# Schematic_v14.net
KiCad netlist of a schematic drawn in EAGLE
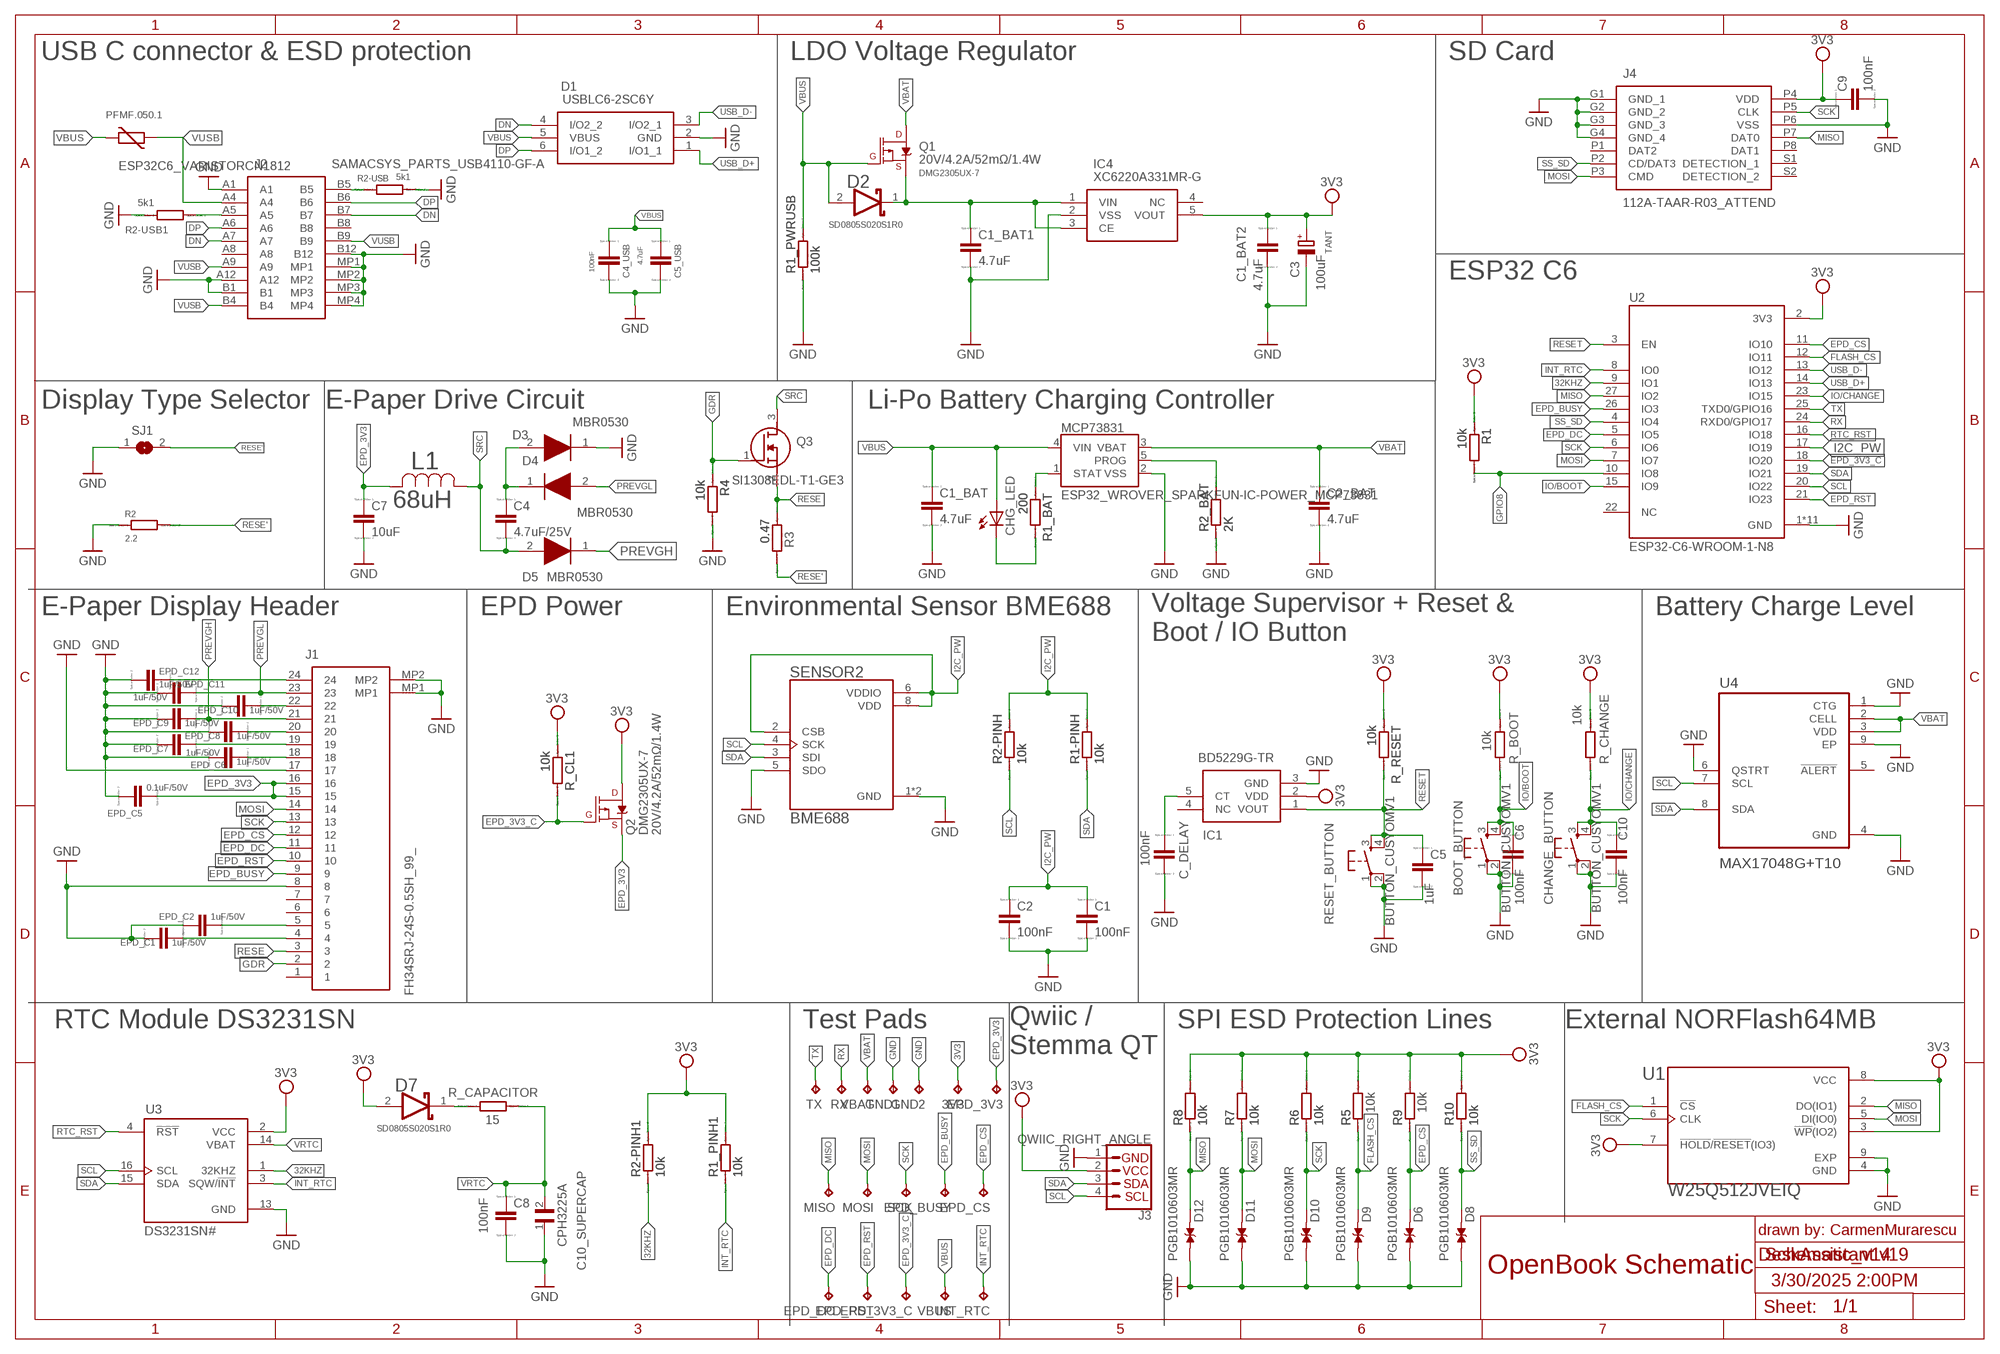
[diagram p0: schematic, sheet 1]

(export (version "E")
  (design (tool "Eeschema 10.0.6"))
  (components
    (comp (ref "3V3")
      (value "TPTP20R")
      (footprint "eagle-import:TP20R")
      (libsource (lib "eagle-import") (part "TPTP20R"))
    )
    (comp (ref "BOOT_BUTTON")
      (value "BUTTON_CUSYOMV1")
      (footprint "eagle-import:MYBUTTON")
      (libsource (lib "eagle-import") (part "BUTTON_CUSYOMV1"))
    )
    (comp (ref "C1")
      (value "100nF")
      (footprint "eagle-import:ESP32_WROVER_EAGLE-LTSPICE_C0402")
      (libsource (lib "eagle-import") (part "EAGLE-LTSPICE_CC0402"))
    )
    (comp (ref "C1_BAT")
      (value "4.7uF")
      (footprint "eagle-import:ESP32_WROVER_EAGLE-LTSPICE_C0402")
      (libsource (lib "eagle-import") (part "EAGLE-LTSPICE_CC0402"))
    )
    (comp (ref "C1_BAT1")
      (value "4.7uF")
      (footprint "eagle-import:ESP32_WROVER_EAGLE-LTSPICE_C0402")
      (libsource (lib "eagle-import") (part "ESP32_WROVER_EAGLE-LTSPICE_CC0402"))
    )
    (comp (ref "C1_BAT2")
      (value "4.7uF")
      (footprint "eagle-import:ESP32_WROVER_EAGLE-LTSPICE_C0402")
      (libsource (lib "eagle-import") (part "ESP32_WROVER_EAGLE-LTSPICE_CC0402"))
    )
    (comp (ref "C2")
      (value "100nF")
      (footprint "eagle-import:ESP32_WROVER_EAGLE-LTSPICE_C0402")
      (libsource (lib "eagle-import") (part "EAGLE-LTSPICE_CC0402"))
    )
    (comp (ref "C2_BAT")
      (value "4.7uF")
      (footprint "eagle-import:ESP32_WROVER_EAGLE-LTSPICE_C0402")
      (libsource (lib "eagle-import") (part "ESP32_WROVER_EAGLE-LTSPICE_CC0402"))
    )
    (comp (ref "C3")
      (value "100uF")
      (footprint "eagle-import:RCL_CT3528")
      (libsource (lib "eagle-import") (part "RCL_CPOL-EUCT3528"))
    )
    (comp (ref "C4")
      (value "4.7uF/25V")
      (footprint "eagle-import:ESP32_WROVER_EAGLE-LTSPICE_C0402")
      (libsource (lib "eagle-import") (part "EAGLE-LTSPICE_CC0402"))
    )
    (comp (ref "C4_USB")
      (value "100nF")
      (footprint "eagle-import:ESP32_WROVER_EAGLE-LTSPICE_C0402")
      (libsource (lib "eagle-import") (part "ESP32_WROVER_EAGLE-LTSPICE_CC0402"))
    )
    (comp (ref "C5")
      (value "1uF")
      (footprint "eagle-import:ESP32_WROVER_EAGLE-LTSPICE_C0402")
      (libsource (lib "eagle-import") (part "EAGLE-LTSPICE_CC0402"))
    )
    (comp (ref "C5_USB")
      (value "4.7uF")
      (footprint "eagle-import:ESP32_WROVER_EAGLE-LTSPICE_C0402")
      (libsource (lib "eagle-import") (part "ESP32_WROVER_EAGLE-LTSPICE_CC0402"))
    )
    (comp (ref "C6")
      (value "100nF")
      (footprint "eagle-import:ESP32_WROVER_EAGLE-LTSPICE_C0402")
      (libsource (lib "eagle-import") (part "ESP32_WROVER_EAGLE-LTSPICE_CC0402"))
    )
    (comp (ref "C7")
      (value "10uF")
      (footprint "eagle-import:ESP32_WROVER_EAGLE-LTSPICE_C0402")
      (libsource (lib "eagle-import") (part "ESP32_WROVER_EAGLE-LTSPICE_CC0402"))
    )
    (comp (ref "C8")
      (value "100nF")
      (footprint "eagle-import:ESP32_WROVER_EAGLE-LTSPICE_C0402")
      (libsource (lib "eagle-import") (part "ESP32_WROVER_EAGLE-LTSPICE_CC0402"))
    )
    (comp (ref "C9")
      (value "100nF")
      (footprint "eagle-import:ESP32_WROVER_EAGLE-LTSPICE_C0402")
      (libsource (lib "eagle-import") (part "EAGLE-LTSPICE_CC0402"))
    )
    (comp (ref "C10")
      (value "100nF")
      (footprint "eagle-import:ESP32_WROVER_EAGLE-LTSPICE_C0402")
      (libsource (lib "eagle-import") (part "ESP32_WROVER_EAGLE-LTSPICE_CC0402"))
    )
    (comp (ref "C10_SUPERCAP")
      (value "CPH3225A")
      (footprint "eagle-import:CAPCP3225X100N")
      (fields (field (name "MF") "Seiko Instruments"))
      (libsource (lib "eagle-import") (part "CPH3225A"))
    )
    (comp (ref "CHANGE_BUTTON")
      (value "BUTTON_CUSYOMV1")
      (footprint "eagle-import:MYBUTTON")
      (libsource (lib "eagle-import") (part "BUTTON_CUSYOMV1"))
    )
    (comp (ref "CHG_LED")
      (value "ADAFRUIT_LEDCHIP-LED0603")
      (footprint "eagle-import:ADAFRUIT_CHIP-LED0603")
      (libsource (lib "eagle-import") (part "ADAFRUIT_LEDCHIP-LED0603"))
    )
    (comp (ref "C_DELAY")
      (value "100nF")
      (footprint "eagle-import:ESP32_WROVER_EAGLE-LTSPICE_C0402")
      (libsource (lib "eagle-import") (part "EAGLE-LTSPICE_CC0402"))
    )
    (comp (ref "D1")
      (value "USBLC6-2SC6Y")
      (footprint "eagle-import:SOT95P280X145-6N")
      (fields (field (name "MF") "STMicroelectronics"))
      (libsource (lib "eagle-import") (part "USBLC6-2SC6Y"))
    )
    (comp (ref "D2")
      (value "ESP32_WROVER_AVX---SD0805S020S1R0_AVX_SD0805S020S1R0_0_0AVX_SD0805S020S1R0_0_0")
      (footprint "eagle-import:ESP32_WROVER_AVX---SD0805S020S1R0_AVX_SD0805S020S1R0_0")
      (fields
        (field (name "DIGIKEY_PART_NUMBER") "478-7800-1-ND")
        (field (name "MF") "AVX")
        (field (name "MOUSER_PART_NUMBER") "581-SD0805S020S1R0")
      )
      (libsource (lib "eagle-import") (part "ESP32_WROVER_AVX---SD0805S020S1R0_AVX_SD0805S020S1R0_0_0AVX_SD0805S020S1R0_0_0"))
    )
    (comp (ref "D3")
      (value "MBR0530")
      (footprint "eagle-import:SOD3716X135N")
      (fields (field (name "MF") "ON Semiconductor"))
      (libsource (lib "eagle-import") (part "MBR0530"))
    )
    (comp (ref "D4")
      (value "MBR0530")
      (footprint "eagle-import:SOD3716X135N")
      (fields (field (name "MF") "ON Semiconductor"))
      (libsource (lib "eagle-import") (part "MBR0530"))
    )
    (comp (ref "D5")
      (value "MBR0530")
      (footprint "eagle-import:SOD3716X135N")
      (fields (field (name "MF") "ON Semiconductor"))
      (libsource (lib "eagle-import") (part "MBR0530"))
    )
    (comp (ref "D6")
      (value "PGB1010603MR")
      (footprint "eagle-import:DIOC1608X36N")
      (fields (field (name "MF") "Littelfuse Inc."))
      (libsource (lib "eagle-import") (part "PGB1010603MR"))
    )
    (comp (ref "D7")
      (value "SD0805S020S1R0")
      (footprint "eagle-import:ESP32_WROVER_AVX---SD0805S020S1R0_AVX_SD0805S020S1R0_0")
      (fields
        (field (name "DIGIKEY_PART_NUMBER") "478-7800-1-ND")
        (field (name "MF") "AVX")
        (field (name "MOUSER_PART_NUMBER") "581-SD0805S020S1R0")
      )
      (libsource (lib "eagle-import") (part "ESP32_WROVER_AVX---SD0805S020S1R0_AVX_SD0805S020S1R0_0_0AVX_SD0805S020S1R0_0_0"))
    )
    (comp (ref "D8")
      (value "PGB1010603MR")
      (footprint "eagle-import:DIOC1608X36N")
      (fields (field (name "MF") "Littelfuse Inc."))
      (libsource (lib "eagle-import") (part "PGB1010603MR"))
    )
    (comp (ref "D9")
      (value "PGB1010603MR")
      (footprint "eagle-import:DIOC1608X36N")
      (fields (field (name "MF") "Littelfuse Inc."))
      (libsource (lib "eagle-import") (part "PGB1010603MR"))
    )
    (comp (ref "D10")
      (value "PGB1010603MR")
      (footprint "eagle-import:DIOC1608X36N")
      (fields (field (name "MF") "Littelfuse Inc."))
      (libsource (lib "eagle-import") (part "PGB1010603MR"))
    )
    (comp (ref "D11")
      (value "PGB1010603MR")
      (footprint "eagle-import:DIOC1608X36N")
      (fields (field (name "MF") "Littelfuse Inc."))
      (libsource (lib "eagle-import") (part "PGB1010603MR"))
    )
    (comp (ref "D12")
      (value "PGB1010603MR")
      (footprint "eagle-import:DIOC1608X36N")
      (fields (field (name "MF") "Littelfuse Inc."))
      (libsource (lib "eagle-import") (part "PGB1010603MR"))
    )
    (comp (ref "EPD_3V3")
      (value "TPTP20R")
      (footprint "eagle-import:TP20R")
      (libsource (lib "eagle-import") (part "TPTP20R"))
    )
    (comp (ref "EPD_3V3_C")
      (value "TPTP20R")
      (footprint "eagle-import:TP20R")
      (libsource (lib "eagle-import") (part "TPTP20R"))
    )
    (comp (ref "EPD_BUSY")
      (value "TPTP20R")
      (footprint "eagle-import:TP20R")
      (libsource (lib "eagle-import") (part "TPTP20R"))
    )
    (comp (ref "EPD_C1")
      (value "1uF/50V")
      (footprint "eagle-import:ESP32_WROVER_EAGLE-LTSPICE_C0402")
      (libsource (lib "eagle-import") (part "EAGLE-LTSPICE_CC0402"))
    )
    (comp (ref "EPD_C2")
      (value "1uF/50V")
      (footprint "eagle-import:ESP32_WROVER_EAGLE-LTSPICE_C0402")
      (libsource (lib "eagle-import") (part "EAGLE-LTSPICE_CC0402"))
    )
    (comp (ref "EPD_C5")
      (value "0.1uF/50V")
      (footprint "eagle-import:ESP32_WROVER_EAGLE-LTSPICE_C0402")
      (libsource (lib "eagle-import") (part "EAGLE-LTSPICE_CC0402"))
    )
    (comp (ref "EPD_C6")
      (value "1uF/50V")
      (footprint "eagle-import:ESP32_WROVER_EAGLE-LTSPICE_C0402")
      (libsource (lib "eagle-import") (part "EAGLE-LTSPICE_CC0402"))
    )
    (comp (ref "EPD_C7")
      (value "1uF/50V")
      (footprint "eagle-import:ESP32_WROVER_EAGLE-LTSPICE_C0402")
      (libsource (lib "eagle-import") (part "EAGLE-LTSPICE_CC0402"))
    )
    (comp (ref "EPD_C8")
      (value "1uF/50V")
      (footprint "eagle-import:ESP32_WROVER_EAGLE-LTSPICE_C0402")
      (libsource (lib "eagle-import") (part "EAGLE-LTSPICE_CC0402"))
    )
    (comp (ref "EPD_C9")
      (value "1uF/50V")
      (footprint "eagle-import:ESP32_WROVER_EAGLE-LTSPICE_C0402")
      (libsource (lib "eagle-import") (part "EAGLE-LTSPICE_CC0402"))
    )
    (comp (ref "EPD_C10")
      (value "1uF/50V")
      (footprint "eagle-import:ESP32_WROVER_EAGLE-LTSPICE_C0402")
      (libsource (lib "eagle-import") (part "EAGLE-LTSPICE_CC0402"))
    )
    (comp (ref "EPD_C11")
      (value "1uF/50V")
      (footprint "eagle-import:ESP32_WROVER_EAGLE-LTSPICE_C0402")
      (libsource (lib "eagle-import") (part "EAGLE-LTSPICE_CC0402"))
    )
    (comp (ref "EPD_C12")
      (value "1uF/50V")
      (footprint "eagle-import:ESP32_WROVER_EAGLE-LTSPICE_C0402")
      (libsource (lib "eagle-import") (part "EAGLE-LTSPICE_CC0402"))
    )
    (comp (ref "EPD_CS")
      (value "TPTP20R")
      (footprint "eagle-import:TP20R")
      (libsource (lib "eagle-import") (part "TPTP20R"))
    )
    (comp (ref "EPD_DC")
      (value "TPTP20R")
      (footprint "eagle-import:TP20R")
      (libsource (lib "eagle-import") (part "TPTP20R"))
    )
    (comp (ref "EPD_RST")
      (value "TPTP20R")
      (footprint "eagle-import:TP20R")
      (libsource (lib "eagle-import") (part "TPTP20R"))
    )
    (comp (ref "GND1")
      (value "TPTP20R")
      (footprint "eagle-import:TP20R")
      (libsource (lib "eagle-import") (part "TPTP20R"))
    )
    (comp (ref "GND2")
      (value "TPTP20R")
      (footprint "eagle-import:TP20R")
      (libsource (lib "eagle-import") (part "TPTP20R"))
    )
    (comp (ref "IC1")
      (value "BD5229G-TR")
      (footprint "eagle-import:SOT95P280X120-5N")
      (fields (field (name "MOUSER_PART_NUMBER") "755-BD5229G-TR"))
      (libsource (lib "eagle-import") (part "BD5229G-TR"))
    )
    (comp (ref "IC4")
      (value "XC6220A331MR-G")
      (footprint "eagle-import:SOT95P280X120-5N")
      (fields (field (name "MOUSER_PART_NUMBER") "865-XC6220A331MR-G"))
      (libsource (lib "eagle-import") (part "XC6220A331MR-G"))
    )
    (comp (ref "INT_RTC")
      (value "TPTP20R")
      (footprint "eagle-import:TP20R")
      (libsource (lib "eagle-import") (part "TPTP20R"))
    )
    (comp (ref "J1")
      (value "FH34SRJ-24S-0.5SH_99_")
      (footprint "eagle-import:FH34SRJ24S05SH99")
      (fields
        (field (name "MANUFACTURER_PART_NUMBER") "FH34SRJ-24S-0.5SH(99)")
        (field (name "MOUSER_PART_NUMBER") "798-FH34SRJ24S05SH99")
      )
      (libsource (lib "eagle-import") (part "FH34SRJ-24S-0.5SH_99_"))
    )
    (comp (ref "J2")
      (value "SAMACSYS_PARTS_USB4110-GF-A")
      (footprint "eagle-import:SAMACSYS_PARTS_USB4110GFA")
      (fields
        (field (name "MANUFACTURER_PART_NUMBER") "USB4110-GF-A")
        (field (name "MOUSER_PART_NUMBER") "640-USB4110-GF-A")
      )
      (libsource (lib "eagle-import") (part "SAMACSYS_PARTS_USB4110-GF-A"))
    )
    (comp (ref "J3")
      (value "QWIIC_RIGHT_ANGLE")
      (footprint "eagle-import:JST04_1MM_RA")
      (libsource (lib "eagle-import") (part "QWIIC_CONNECTORJS-1MM"))
    )
    (comp (ref "J4")
      (value "112A-TAAR-R03_ATTEND")
      (footprint "eagle-import:112ATAARR03ATTEND")
      (fields (field (name "MANUFACTURER_PART_NUMBER") "112A-TAAR-R03 ATTEND"))
      (libsource (lib "eagle-import") (part "112A-TAAR-R03_ATTEND"))
    )
    (comp (ref "L1")
      (value "68uH")
      (footprint "eagle-import:IND_4828-WE-TPC_WRE")
      (fields
        (field (name "MANUFACTURER_PART_NUMBER") "744043680")
        (field (name "COPYRIGHT") "Copyright (C) 2024 Ultra Librarian. All rights reserved.")
      )
      (libsource (lib "eagle-import") (part "744043680IND_4828-WE-TPC_WRE"))
    )
    (comp (ref "MCP73831")
      (value "ESP32_WROVER_SPARKFUN-IC-POWER_MCP73831")
      (footprint "eagle-import:ESP32_WROVER_SPARKFUN-IC-POWER_SOT23-5")
      (libsource (lib "eagle-import") (part "ESP32_WROVER_SPARKFUN-IC-POWER_MCP73831"))
    )
    (comp (ref "MISO")
      (value "TPTP20R")
      (footprint "eagle-import:TP20R")
      (libsource (lib "eagle-import") (part "TPTP20R"))
    )
    (comp (ref "MOSI")
      (value "TPTP20R")
      (footprint "eagle-import:TP20R")
      (libsource (lib "eagle-import") (part "TPTP20R"))
    )
    (comp (ref "PFMF.050.1")
      (value "ESP32C6_VARISTORCN1812")
      (footprint "eagle-import:ESP32C6_VARISTOR_CT_CN1812")
      (libsource (lib "eagle-import") (part "ESP32C6_VARISTORCN1812"))
    )
    (comp (ref "Q1")
      (value "20V/4.2A/52mΩ/1.4W")
      (footprint "eagle-import:ESP32_WROVER_SPARKFUN-DISCRETESEMI_SOT23-3")
      (libsource (lib "eagle-import") (part "ESP32_WROVER_SPARKFUN-DISCRETESEMI_MOSFET_PCH-DMG2305UX-7"))
    )
    (comp (ref "Q2")
      (value "20V/4.2A/52mΩ/1.4W")
      (footprint "eagle-import:ESP32_WROVER_SPARKFUN-DISCRETESEMI_SOT23-3")
      (libsource (lib "eagle-import") (part "ESP32_WROVER_SPARKFUN-DISCRETESEMI_MOSFET_PCH-DMG2305UX-7"))
    )
    (comp (ref "Q3")
      (value "SI1308EDL-T1-GE3")
      (footprint "eagle-import:SOT65P210X110-3N")
      (fields (field (name "MF") "Vishay Siliconix"))
      (libsource (lib "eagle-import") (part "SI1308EDL-T1-GE3"))
    )
    (comp (ref "R1")
      (value "10k")
      (footprint "eagle-import:ESP32_WROVER_EAGLE-LTSPICE_R0402")
      (libsource (lib "eagle-import") (part "ESP32_WROVER_EAGLE-LTSPICE_RR0402"))
    )
    (comp (ref "R1-PINH")
      (value "10k")
      (footprint "eagle-import:ESP32_WROVER_EAGLE-LTSPICE_R0402")
      (libsource (lib "eagle-import") (part "ESP32_WROVER_EAGLE-LTSPICE_RR0402"))
    )
    (comp (ref "R1_BAT")
      (value "200")
      (footprint "eagle-import:ESP32_WROVER_EAGLE-LTSPICE_R0402")
      (libsource (lib "eagle-import") (part "ESP32_WROVER_EAGLE-LTSPICE_RR0402"))
    )
    (comp (ref "R1_PINH1")
      (value "10k")
      (footprint "eagle-import:ESP32_WROVER_EAGLE-LTSPICE_R0402")
      (libsource (lib "eagle-import") (part "ESP32_WROVER_EAGLE-LTSPICE_RR0402"))
    )
    (comp (ref "R1_PWRUSB")
      (value "100k")
      (footprint "eagle-import:ESP32_WROVER_EAGLE-LTSPICE_R0402")
      (libsource (lib "eagle-import") (part "ESP32_WROVER_EAGLE-LTSPICE_RR0402"))
    )
    (comp (ref "R2")
      (value "2.2")
      (footprint "eagle-import:ESP32_WROVER_EAGLE-LTSPICE_R0402")
      (libsource (lib "eagle-import") (part "ESP32_WROVER_EAGLE-LTSPICE_RR0402"))
    )
    (comp (ref "R2-PINH")
      (value "10k")
      (footprint "eagle-import:ESP32_WROVER_EAGLE-LTSPICE_R0402")
      (libsource (lib "eagle-import") (part "ESP32_WROVER_EAGLE-LTSPICE_RR0402"))
    )
    (comp (ref "R2-PINH1")
      (value "10k")
      (footprint "eagle-import:ESP32_WROVER_EAGLE-LTSPICE_R0402")
      (libsource (lib "eagle-import") (part "ESP32_WROVER_EAGLE-LTSPICE_RR0402"))
    )
    (comp (ref "R2-USB")
      (value "5k1")
      (footprint "eagle-import:ESP32_WROVER_EAGLE-LTSPICE_R0402")
      (libsource (lib "eagle-import") (part "ESP32_WROVER_EAGLE-LTSPICE_RR0402"))
    )
    (comp (ref "R2-USB1")
      (value "5k1")
      (footprint "eagle-import:ESP32_WROVER_EAGLE-LTSPICE_R0402")
      (libsource (lib "eagle-import") (part "ESP32_WROVER_EAGLE-LTSPICE_RR0402"))
    )
    (comp (ref "R2_BAT")
      (value "2K")
      (footprint "eagle-import:ESP32_WROVER_EAGLE-LTSPICE_R0402")
      (libsource (lib "eagle-import") (part "ESP32_WROVER_EAGLE-LTSPICE_RR0402"))
    )
    (comp (ref "R3")
      (value "0.47")
      (footprint "eagle-import:ESP32_WROVER_EAGLE-LTSPICE_R0402")
      (libsource (lib "eagle-import") (part "ESP32_WROVER_EAGLE-LTSPICE_RR0402"))
    )
    (comp (ref "R4")
      (value "10k")
      (footprint "eagle-import:ESP32_WROVER_EAGLE-LTSPICE_R0402")
      (libsource (lib "eagle-import") (part "ESP32_WROVER_EAGLE-LTSPICE_RR0402"))
    )
    (comp (ref "R5")
      (value "10k")
      (footprint "eagle-import:ESP32_WROVER_EAGLE-LTSPICE_R0402")
      (libsource (lib "eagle-import") (part "ESP32_WROVER_EAGLE-LTSPICE_RR0402"))
    )
    (comp (ref "R6")
      (value "10k")
      (footprint "eagle-import:ESP32_WROVER_EAGLE-LTSPICE_R0402")
      (libsource (lib "eagle-import") (part "ESP32_WROVER_EAGLE-LTSPICE_RR0402"))
    )
    (comp (ref "R7")
      (value "10k")
      (footprint "eagle-import:ESP32_WROVER_EAGLE-LTSPICE_R0402")
      (libsource (lib "eagle-import") (part "ESP32_WROVER_EAGLE-LTSPICE_RR0402"))
    )
    (comp (ref "R8")
      (value "10k")
      (footprint "eagle-import:ESP32_WROVER_EAGLE-LTSPICE_R0402")
      (libsource (lib "eagle-import") (part "ESP32_WROVER_EAGLE-LTSPICE_RR0402"))
    )
    (comp (ref "R9")
      (value "10k")
      (footprint "eagle-import:ESP32_WROVER_EAGLE-LTSPICE_R0402")
      (libsource (lib "eagle-import") (part "ESP32_WROVER_EAGLE-LTSPICE_RR0402"))
    )
    (comp (ref "R10")
      (value "10k")
      (footprint "eagle-import:ESP32_WROVER_EAGLE-LTSPICE_R0402")
      (libsource (lib "eagle-import") (part "ESP32_WROVER_EAGLE-LTSPICE_RR0402"))
    )
    (comp (ref "RESET_BUTTON")
      (value "BUTTON_CUSYOMV1")
      (footprint "eagle-import:MYBUTTON")
      (libsource (lib "eagle-import") (part "BUTTON_CUSYOMV1"))
    )
    (comp (ref "RX")
      (value "TPTP20R")
      (footprint "eagle-import:TP20R")
      (libsource (lib "eagle-import") (part "TPTP20R"))
    )
    (comp (ref "R_BOOT")
      (value "10k")
      (footprint "eagle-import:ESP32_WROVER_EAGLE-LTSPICE_R0402")
      (libsource (lib "eagle-import") (part "ESP32_WROVER_EAGLE-LTSPICE_RR0402"))
    )
    (comp (ref "R_CAPACITOR")
      (value "15")
      (footprint "eagle-import:ESP32_WROVER_EAGLE-LTSPICE_R0402")
      (libsource (lib "eagle-import") (part "ESP32_WROVER_EAGLE-LTSPICE_RR0402"))
    )
    (comp (ref "R_CHANGE")
      (value "10k")
      (footprint "eagle-import:ESP32_WROVER_EAGLE-LTSPICE_R0402")
      (libsource (lib "eagle-import") (part "ESP32_WROVER_EAGLE-LTSPICE_RR0402"))
    )
    (comp (ref "R_CL1")
      (value "10k")
      (footprint "eagle-import:ESP32_WROVER_EAGLE-LTSPICE_R0402")
      (libsource (lib "eagle-import") (part "ESP32_WROVER_EAGLE-LTSPICE_RR0402"))
    )
    (comp (ref "R_RESET")
      (value "10k")
      (footprint "eagle-import:ESP32_WROVER_EAGLE-LTSPICE_R0402")
      (libsource (lib "eagle-import") (part "ESP32_WROVER_EAGLE-LTSPICE_RR0402"))
    )
    (comp (ref "SCK")
      (value "TPTP20R")
      (footprint "eagle-import:TP20R")
      (libsource (lib "eagle-import") (part "TPTP20R"))
    )
    (comp (ref "SENSOR2")
      (value "BME688")
      (footprint "eagle-import:ESP32_WROVER_BME680_PSON80P300X300X100-8N")
      (fields (field (name "MF") "Bosch Sensortec") (field (name "MP") "BME680"))
      (libsource (lib "eagle-import") (part "ESP32_WROVER_BME680_BME680"))
    )
    (comp (ref "SJ1") (value "SJ") (footprint "eagle-import:SJ") (libsource (lib "eagle-import") (part "SJ")))
    (comp (ref "TX")
      (value "TPTP20R")
      (footprint "eagle-import:TP20R")
      (libsource (lib "eagle-import") (part "TPTP20R"))
    )
    (comp (ref "U1")
      (value "W25Q512JVEIQ")
      (footprint "eagle-import:SON127P600X800X80-9N")
      (fields (field (name "MF") "Winbond Electronics"))
      (libsource (lib "eagle-import") (part "W25Q512JVEIQ"))
    )
    (comp (ref "U2")
      (value "ESP32-C6-WROOM-1-N8")
      (footprint "eagle-import:XCVR_ESP32-C6-WROOM-1-N8")
      (fields (field (name "MF") "Espressif Systems"))
      (libsource (lib "eagle-import") (part "ESP32-C6-WROOM-1-N8"))
    )
    (comp (ref "U3")
      (value "DS3231SN#")
      (footprint "eagle-import:SOIC127P1032X265-16N")
      (fields (field (name "MF") "Analog Devices"))
      (libsource (lib "eagle-import") (part "DS3231SN#"))
    )
    (comp (ref "U4")
      (value "MAX17048G+T10")
      (footprint "eagle-import:SON50P200X200X80-9N")
      (fields (field (name "MF") "Analog Devices"))
      (libsource (lib "eagle-import") (part "MAX17048G+T10"))
    )
    (comp (ref "VBAT")
      (value "TPTP20R")
      (footprint "eagle-import:TP20R")
      (libsource (lib "eagle-import") (part "TPTP20R"))
    )
    (comp (ref "VBUS")
      (value "TPTP20R")
      (footprint "eagle-import:TP20R")
      (libsource (lib "eagle-import") (part "TPTP20R"))
    )
  )
  (nets
    (net (code "1") (name "3V3") (class "Default")
      (node (ref "3V3") (pin "TP") (pinfunction "TP_TP") (pintype "input"))
      (node (ref "C1_BAT2") (pin "1") (pinfunction "1_1") (pintype "passive"))
      (node (ref "C3") (pin "+") (pinfunction "+_+") (pintype "passive"))
      (node (ref "C9") (pin "1") (pinfunction "1_1") (pintype "passive"))
      (node (ref "D7") (pin "2") (pinfunction "ANODE_2") (pintype "bidirectional"))
      (node (ref "IC1") (pin "2") (pinfunction "VDD_2") (pintype "bidirectional"))
      (node (ref "IC4") (pin "5") (pinfunction "VOUT_5") (pintype "bidirectional"))
      (node (ref "J3") (pin "2") (pinfunction "2_2") (pintype "power_in"))
      (node (ref "J4") (pin "P4") (pinfunction "VDD_P4") (pintype "bidirectional"))
      (node (ref "Q2") (pin "3") (pinfunction "D_3") (pintype "bidirectional"))
      (node (ref "R1") (pin "1") (pinfunction "1_1") (pintype "passive"))
      (node (ref "R10") (pin "2") (pinfunction "2_2") (pintype "passive"))
      (node (ref "R1_PINH1") (pin "2") (pinfunction "2_2") (pintype "passive"))
      (node (ref "R2-PINH1") (pin "2") (pinfunction "2_2") (pintype "passive"))
      (node (ref "R5") (pin "2") (pinfunction "2_2") (pintype "passive"))
      (node (ref "R6") (pin "2") (pinfunction "2_2") (pintype "passive"))
      (node (ref "R7") (pin "2") (pinfunction "2_2") (pintype "passive"))
      (node (ref "R8") (pin "2") (pinfunction "2_2") (pintype "passive"))
      (node (ref "R9") (pin "2") (pinfunction "2_2") (pintype "passive"))
      (node (ref "R_BOOT") (pin "2") (pinfunction "2_2") (pintype "passive"))
      (node (ref "R_CHANGE") (pin "2") (pinfunction "2_2") (pintype "passive"))
      (node (ref "R_CL1") (pin "1") (pinfunction "1_1") (pintype "passive"))
      (node (ref "R_RESET") (pin "1") (pinfunction "1_1") (pintype "passive"))
      (node (ref "U1") (pin "3") (pinfunction "~{WP}(IO2)_3") (pintype "bidirectional"))
      (node (ref "U1") (pin "7") (pinfunction "~{HOLD}/~{RESET}(IO3)_7") (pintype "bidirectional"))
      (node (ref "U1") (pin "8") (pinfunction "VCC_8") (pintype "power_in"))
      (node (ref "U2") (pin "2") (pinfunction "3V3_2") (pintype "power_in"))
      (node (ref "U3") (pin "2") (pinfunction "VCC_2") (pintype "power_in"))
    )
    (net (code "2") (name "32KHZ") (class "Default")
      (node (ref "R2-PINH1") (pin "1") (pinfunction "1_1") (pintype "passive"))
      (node (ref "U2") (pin "9") (pinfunction "IO1_9") (pintype "bidirectional"))
      (node (ref "U3") (pin "1") (pinfunction "32KHZ_1") (pintype "output"))
    )
    (net (code "3") (name "DN") (class "Default")
      (node (ref "D1") (pin "4") (pinfunction "I/O2_2_4") (pintype "bidirectional"))
      (node (ref "J2") (pin "A7") (pinfunction "A7_A7") (pintype "bidirectional"))
      (node (ref "J2") (pin "B7") (pinfunction "B7_B7") (pintype "bidirectional"))
    )
    (net (code "4") (name "DP") (class "Default")
      (node (ref "D1") (pin "6") (pinfunction "I/O1_2_6") (pintype "bidirectional"))
      (node (ref "J2") (pin "A6") (pinfunction "A6_A6") (pintype "bidirectional"))
      (node (ref "J2") (pin "B6") (pinfunction "B6_B6") (pintype "bidirectional"))
    )
    (net (code "5") (name "EPD_3V3") (class "Default")
      (node (ref "C7") (pin "1") (pinfunction "1_1") (pintype "passive"))
      (node (ref "EPD_3V3") (pin "TP") (pinfunction "TP_TP") (pintype "input"))
      (node (ref "EPD_C5") (pin "1") (pinfunction "1_1") (pintype "passive"))
      (node (ref "J1") (pin "15") (pinfunction "15_15") (pintype "bidirectional"))
      (node (ref "J1") (pin "16") (pinfunction "16_16") (pintype "bidirectional"))
      (node (ref "L1") (pin "2") (pinfunction "2_2") (pintype "passive"))
      (node (ref "Q2") (pin "2") (pinfunction "S_2") (pintype "bidirectional"))
    )
    (net (code "6") (name "EPD_3V3_C") (class "Default")
      (node (ref "EPD_3V3_C") (pin "TP") (pinfunction "TP_TP") (pintype "input"))
      (node (ref "Q2") (pin "1") (pinfunction "G_1") (pintype "bidirectional"))
      (node (ref "R_CL1") (pin "2") (pinfunction "2_2") (pintype "passive"))
      (node (ref "U2") (pin "18") (pinfunction "IO20_18") (pintype "bidirectional"))
    )
    (net (code "7") (name "EPD_BUSY") (class "Default")
      (node (ref "EPD_BUSY") (pin "TP") (pinfunction "TP_TP") (pintype "input"))
      (node (ref "J1") (pin "9") (pinfunction "9_9") (pintype "bidirectional"))
      (node (ref "U2") (pin "26") (pinfunction "IO3_26") (pintype "bidirectional"))
    )
    (net (code "8") (name "EPD_CS") (class "Default")
      (node (ref "D6") (pin "2") (pinfunction "2_2") (pintype "passive"))
      (node (ref "EPD_CS") (pin "TP") (pinfunction "TP_TP") (pintype "input"))
      (node (ref "J1") (pin "12") (pinfunction "12_12") (pintype "bidirectional"))
      (node (ref "R9") (pin "1") (pinfunction "1_1") (pintype "passive"))
      (node (ref "U2") (pin "11") (pinfunction "IO10_11") (pintype "bidirectional"))
    )
    (net (code "9") (name "EPD_DC") (class "Default")
      (node (ref "EPD_DC") (pin "TP") (pinfunction "TP_TP") (pintype "input"))
      (node (ref "J1") (pin "11") (pinfunction "11_11") (pintype "bidirectional"))
      (node (ref "U2") (pin "5") (pinfunction "IO5_5") (pintype "bidirectional"))
    )
    (net (code "10") (name "EPD_RST") (class "Default")
      (node (ref "EPD_RST") (pin "TP") (pinfunction "TP_TP") (pintype "input"))
      (node (ref "J1") (pin "10") (pinfunction "10_10") (pintype "bidirectional"))
      (node (ref "U2") (pin "21") (pinfunction "IO23_21") (pintype "bidirectional"))
    )
    (net (code "11") (name "FLASH_CS") (class "Default")
      (node (ref "D9") (pin "2") (pinfunction "2_2") (pintype "passive"))
      (node (ref "R5") (pin "1") (pinfunction "1_1") (pintype "passive"))
      (node (ref "U1") (pin "1") (pinfunction "~{CS}_1") (pintype "input"))
      (node (ref "U2") (pin "12") (pinfunction "IO11_12") (pintype "bidirectional"))
    )
    (net (code "12") (name "GDR") (class "Default")
      (node (ref "J1") (pin "2") (pinfunction "2_2") (pintype "bidirectional"))
      (node (ref "Q3") (pin "1") (pinfunction "G_1") (pintype "bidirectional"))
      (node (ref "R4") (pin "1") (pinfunction "1_1") (pintype "passive"))
    )
    (net (code "13") (name "GND") (class "Default")
      (node (ref "BOOT_BUTTON") (pin "1") (pinfunction "1_1") (pintype "passive"))
      (node (ref "BOOT_BUTTON") (pin "2") (pinfunction "2_2") (pintype "passive"))
      (node (ref "C1") (pin "2") (pinfunction "2_2") (pintype "passive"))
      (node (ref "C10") (pin "2") (pinfunction "2_2") (pintype "passive"))
      (node (ref "C10_SUPERCAP") (pin "1") (pinfunction "1_1") (pintype "passive"))
      (node (ref "C1_BAT") (pin "2") (pinfunction "2_2") (pintype "passive"))
      (node (ref "C1_BAT1") (pin "2") (pinfunction "2_2") (pintype "passive"))
      (node (ref "C1_BAT2") (pin "2") (pinfunction "2_2") (pintype "passive"))
      (node (ref "C2") (pin "2") (pinfunction "2_2") (pintype "passive"))
      (node (ref "C2_BAT") (pin "2") (pinfunction "2_2") (pintype "passive"))
      (node (ref "C3") (pin "-") (pinfunction "-_-") (pintype "passive"))
      (node (ref "C4_USB") (pin "2") (pinfunction "2_2") (pintype "passive"))
      (node (ref "C5") (pin "2") (pinfunction "2_2") (pintype "passive"))
      (node (ref "C5_USB") (pin "2") (pinfunction "2_2") (pintype "passive"))
      (node (ref "C6") (pin "2") (pinfunction "2_2") (pintype "passive"))
      (node (ref "C7") (pin "2") (pinfunction "2_2") (pintype "passive"))
      (node (ref "C8") (pin "2") (pinfunction "2_2") (pintype "passive"))
      (node (ref "C9") (pin "2") (pinfunction "2_2") (pintype "passive"))
      (node (ref "CHANGE_BUTTON") (pin "1") (pinfunction "1_1") (pintype "passive"))
      (node (ref "CHANGE_BUTTON") (pin "2") (pinfunction "2_2") (pintype "passive"))
      (node (ref "C_DELAY") (pin "2") (pinfunction "2_2") (pintype "passive"))
      (node (ref "D1") (pin "2") (pinfunction "GND_2") (pintype "bidirectional"))
      (node (ref "D10") (pin "1") (pinfunction "1_1") (pintype "passive"))
      (node (ref "D11") (pin "1") (pinfunction "1_1") (pintype "passive"))
      (node (ref "D12") (pin "1") (pinfunction "1_1") (pintype "passive"))
      (node (ref "D4") (pin "1") (pinfunction "K_1") (pintype "bidirectional"))
      (node (ref "D6") (pin "1") (pinfunction "1_1") (pintype "passive"))
      (node (ref "D8") (pin "1") (pinfunction "1_1") (pintype "passive"))
      (node (ref "D9") (pin "1") (pinfunction "1_1") (pintype "passive"))
      (node (ref "EPD_C1") (pin "2") (pinfunction "2_2") (pintype "passive"))
      (node (ref "EPD_C10") (pin "2") (pinfunction "2_2") (pintype "passive"))
      (node (ref "EPD_C11") (pin "2") (pinfunction "2_2") (pintype "passive"))
      (node (ref "EPD_C12") (pin "2") (pinfunction "2_2") (pintype "passive"))
      (node (ref "EPD_C2") (pin "2") (pinfunction "2_2") (pintype "passive"))
      (node (ref "EPD_C5") (pin "2") (pinfunction "2_2") (pintype "passive"))
      (node (ref "EPD_C6") (pin "2") (pinfunction "2_2") (pintype "passive"))
      (node (ref "EPD_C7") (pin "2") (pinfunction "2_2") (pintype "passive"))
      (node (ref "EPD_C8") (pin "2") (pinfunction "2_2") (pintype "passive"))
      (node (ref "EPD_C9") (pin "2") (pinfunction "2_2") (pintype "passive"))
      (node (ref "GND1") (pin "TP") (pinfunction "TP_TP") (pintype "input"))
      (node (ref "GND2") (pin "TP") (pinfunction "TP_TP") (pintype "input"))
      (node (ref "IC1") (pin "3") (pinfunction "GND_3") (pintype "bidirectional"))
      (node (ref "IC4") (pin "2") (pinfunction "VSS_2") (pintype "bidirectional"))
      (node (ref "J1") (pin "17") (pinfunction "17_17") (pintype "bidirectional"))
      (node (ref "J1") (pin "8") (pinfunction "8_8") (pintype "bidirectional"))
      (node (ref "J1") (pin "MP1") (pinfunction "MP1_MP1") (pintype "bidirectional"))
      (node (ref "J1") (pin "MP2") (pinfunction "MP2_MP2") (pintype "bidirectional"))
      (node (ref "J2") (pin "A1") (pinfunction "A1_A1") (pintype "bidirectional"))
      (node (ref "J2") (pin "A12") (pinfunction "A12_A12") (pintype "bidirectional"))
      (node (ref "J2") (pin "B1") (pinfunction "B1_B1") (pintype "bidirectional"))
      (node (ref "J2") (pin "B12") (pinfunction "B12_B12") (pintype "bidirectional"))
      (node (ref "J2") (pin "MP1") (pinfunction "MP1_MP1") (pintype "bidirectional"))
      (node (ref "J2") (pin "MP2") (pinfunction "MP2_MP2") (pintype "bidirectional"))
      (node (ref "J2") (pin "MP3") (pinfunction "MP3_MP3") (pintype "bidirectional"))
      (node (ref "J2") (pin "MP4") (pinfunction "MP4_MP4") (pintype "bidirectional"))
      (node (ref "J3") (pin "1") (pinfunction "1_1") (pintype "power_in"))
      (node (ref "J4") (pin "G1") (pinfunction "GND_1_G1") (pintype "bidirectional"))
      (node (ref "J4") (pin "G2") (pinfunction "GND_2_G2") (pintype "bidirectional"))
      (node (ref "J4") (pin "G3") (pinfunction "GND_3_G3") (pintype "bidirectional"))
      (node (ref "J4") (pin "G4") (pinfunction "GND_4_G4") (pintype "bidirectional"))
      (node (ref "J4") (pin "P6") (pinfunction "VSS_P6") (pintype "bidirectional"))
      (node (ref "MCP73831") (pin "2") (pinfunction "VSS_2") (pintype "power_in"))
      (node (ref "R1_PWRUSB") (pin "1") (pinfunction "1_1") (pintype "passive"))
      (node (ref "R2") (pin "1") (pinfunction "1_1") (pintype "passive"))
      (node (ref "R2-USB") (pin "2") (pinfunction "2_2") (pintype "passive"))
      (node (ref "R2-USB1") (pin "1") (pinfunction "1_1") (pintype "passive"))
      (node (ref "R2_BAT") (pin "1") (pinfunction "1_1") (pintype "passive"))
      (node (ref "R4") (pin "2") (pinfunction "2_2") (pintype "passive"))
      (node (ref "RESET_BUTTON") (pin "1") (pinfunction "1_1") (pintype "passive"))
      (node (ref "RESET_BUTTON") (pin "2") (pinfunction "2_2") (pintype "passive"))
      (node (ref "SENSOR2") (pin "1") (pinfunction "GND_1") (pintype "power_in"))
      (node (ref "SENSOR2") (pin "5") (pinfunction "SDO_5") (pintype "bidirectional"))
      (node (ref "SENSOR2") (pin "7") (pinfunction "GND_7") (pintype "power_in"))
      (node (ref "SJ1") (pin "1") (pinfunction "1_1") (pintype "passive"))
      (node (ref "U1") (pin "4") (pinfunction "GND_4") (pintype "power_in"))
      (node (ref "U1") (pin "9") (pinfunction "EXP_9") (pintype "passive"))
      (node (ref "U2") (pin "1") (pinfunction "GND_1") (pintype "power_in"))
      (node (ref "U2") (pin "28") (pinfunction "GND_28") (pintype "power_in"))
      (node (ref "U2") (pin "29_1") (pinfunction "GND_29_1") (pintype "power_in"))
      (node (ref "U2") (pin "29_2") (pinfunction "GND_29_2") (pintype "power_in"))
      (node (ref "U2") (pin "29_3") (pinfunction "GND_29_3") (pintype "power_in"))
      (node (ref "U2") (pin "29_4") (pinfunction "GND_29_4") (pintype "power_in"))
      (node (ref "U2") (pin "29_5") (pinfunction "GND_29_5") (pintype "power_in"))
      (node (ref "U2") (pin "29_6") (pinfunction "GND_29_6") (pintype "power_in"))
      (node (ref "U2") (pin "29_7") (pinfunction "GND_29_7") (pintype "power_in"))
      (node (ref "U2") (pin "29_8") (pinfunction "GND_29_8") (pintype "power_in"))
      (node (ref "U2") (pin "29_9") (pinfunction "GND_29_9") (pintype "power_in"))
      (node (ref "U3") (pin "13") (pinfunction "GND_13") (pintype "power_in"))
      (node (ref "U4") (pin "1") (pinfunction "CTG_1") (pintype "power_in"))
      (node (ref "U4") (pin "4") (pinfunction "GND_4") (pintype "power_in"))
      (node (ref "U4") (pin "6") (pinfunction "QSTRT_6") (pintype "input"))
      (node (ref "U4") (pin "9") (pinfunction "EP_9") (pintype "power_in"))
    )
    (net (code "14") (name "GPIO8") (class "Default")
      (node (ref "R1") (pin "2") (pinfunction "2_2") (pintype "passive"))
      (node (ref "U2") (pin "10") (pinfunction "IO8_10") (pintype "bidirectional"))
    )
    (net (code "15") (name "I2C_PW") (class "Default")
      (node (ref "C1") (pin "1") (pinfunction "1_1") (pintype "passive"))
      (node (ref "C2") (pin "1") (pinfunction "1_1") (pintype "passive"))
      (node (ref "R1-PINH") (pin "2") (pinfunction "2_2") (pintype "passive"))
      (node (ref "R2-PINH") (pin "2") (pinfunction "2_2") (pintype "passive"))
      (node (ref "SENSOR2") (pin "2") (pinfunction "CSB_2") (pintype "input"))
      (node (ref "SENSOR2") (pin "6") (pinfunction "VDDIO_6") (pintype "power_in"))
      (node (ref "SENSOR2") (pin "8") (pinfunction "VDD_8") (pintype "power_in"))
      (node (ref "U2") (pin "17") (pinfunction "IO19_17") (pintype "bidirectional"))
    )
    (net (code "16") (name "INT_RTC") (class "Default")
      (node (ref "INT_RTC") (pin "TP") (pinfunction "TP_TP") (pintype "input"))
      (node (ref "R1_PINH1") (pin "1") (pinfunction "1_1") (pintype "passive"))
      (node (ref "U2") (pin "8") (pinfunction "IO0_8") (pintype "bidirectional"))
      (node (ref "U3") (pin "3") (pinfunction "SQW/~{INT}_3") (pintype "output"))
    )
    (net (code "17") (name "IO{slash}BOOT") (class "Default")
      (node (ref "BOOT_BUTTON") (pin "3") (pinfunction "3_3") (pintype "passive"))
      (node (ref "BOOT_BUTTON") (pin "4") (pinfunction "4_4") (pintype "passive"))
      (node (ref "C6") (pin "1") (pinfunction "1_1") (pintype "passive"))
      (node (ref "R_BOOT") (pin "1") (pinfunction "1_1") (pintype "passive"))
      (node (ref "U2") (pin "15") (pinfunction "IO9_15") (pintype "bidirectional"))
    )
    (net (code "18") (name "IO{slash}CHANGE") (class "Default")
      (node (ref "C10") (pin "1") (pinfunction "1_1") (pintype "passive"))
      (node (ref "CHANGE_BUTTON") (pin "3") (pinfunction "3_3") (pintype "passive"))
      (node (ref "CHANGE_BUTTON") (pin "4") (pinfunction "4_4") (pintype "passive"))
      (node (ref "R_CHANGE") (pin "1") (pinfunction "1_1") (pintype "passive"))
      (node (ref "U2") (pin "23") (pinfunction "IO15_23") (pintype "bidirectional"))
    )
    (net (code "19") (name "MISO") (class "Default")
      (node (ref "D12") (pin "2") (pinfunction "2_2") (pintype "passive"))
      (node (ref "J4") (pin "P7") (pinfunction "DAT0_P7") (pintype "bidirectional"))
      (node (ref "MISO") (pin "TP") (pinfunction "TP_TP") (pintype "input"))
      (node (ref "R8") (pin "1") (pinfunction "1_1") (pintype "passive"))
      (node (ref "U1") (pin "2") (pinfunction "DO(IO1)_2") (pintype "bidirectional"))
      (node (ref "U2") (pin "27") (pinfunction "IO2_27") (pintype "bidirectional"))
    )
    (net (code "20") (name "MOSI") (class "Default")
      (node (ref "D11") (pin "2") (pinfunction "2_2") (pintype "passive"))
      (node (ref "J1") (pin "14") (pinfunction "14_14") (pintype "bidirectional"))
      (node (ref "J4") (pin "P3") (pinfunction "CMD_P3") (pintype "bidirectional"))
      (node (ref "MOSI") (pin "TP") (pinfunction "TP_TP") (pintype "input"))
      (node (ref "R7") (pin "1") (pinfunction "1_1") (pintype "passive"))
      (node (ref "U1") (pin "5") (pinfunction "DI(IO0)_5") (pintype "bidirectional"))
      (node (ref "U2") (pin "7") (pinfunction "IO7_7") (pintype "bidirectional"))
    )
    (net (code "21") (name "Net-(CHG_LED-PadC)") (class "Default")
      (node (ref "CHG_LED") (pin "C") (pinfunction "C_C") (pintype "passive"))
      (node (ref "R1_BAT") (pin "2") (pinfunction "2_2") (pintype "passive"))
    )
    (net (code "22") (name "Net-(D2-CATHODE)") (class "Default")
      (node (ref "C1_BAT1") (pin "1") (pinfunction "1_1") (pintype "passive"))
      (node (ref "D2") (pin "1") (pinfunction "CATHODE_1") (pintype "bidirectional"))
      (node (ref "IC4") (pin "1") (pinfunction "VIN_1") (pintype "bidirectional"))
      (node (ref "IC4") (pin "3") (pinfunction "CE_3") (pintype "bidirectional"))
      (node (ref "Q1") (pin "2") (pinfunction "S_2") (pintype "bidirectional"))
    )
    (net (code "23") (name "Net-(D3-K)") (class "Default")
      (node (ref "C4") (pin "1") (pinfunction "1_1") (pintype "passive"))
      (node (ref "D3") (pin "1") (pinfunction "K_1") (pintype "bidirectional"))
      (node (ref "D4") (pin "2") (pinfunction "A_2") (pintype "bidirectional"))
    )
    (net (code "24") (name "Net-(D7-CATHODE)") (class "Default")
      (node (ref "D7") (pin "1") (pinfunction "CATHODE_1") (pintype "bidirectional"))
      (node (ref "R_CAPACITOR") (pin "2") (pinfunction "2_2") (pintype "passive"))
    )
    (net (code "25") (name "Net-(EPD_C1-Pad1)") (class "Default")
      (node (ref "EPD_C1") (pin "1") (pinfunction "1_1") (pintype "passive"))
      (node (ref "J1") (pin "4") (pinfunction "4_4") (pintype "bidirectional"))
    )
    (net (code "26") (name "Net-(EPD_C2-Pad1)") (class "Default")
      (node (ref "EPD_C2") (pin "1") (pinfunction "1_1") (pintype "passive"))
      (node (ref "J1") (pin "5") (pinfunction "5_5") (pintype "bidirectional"))
    )
    (net (code "27") (name "Net-(EPD_C6-Pad1)") (class "Default")
      (node (ref "EPD_C6") (pin "1") (pinfunction "1_1") (pintype "passive"))
      (node (ref "J1") (pin "18") (pinfunction "18_18") (pintype "bidirectional"))
    )
    (net (code "28") (name "Net-(EPD_C7-Pad1)") (class "Default")
      (node (ref "EPD_C7") (pin "1") (pinfunction "1_1") (pintype "passive"))
      (node (ref "J1") (pin "19") (pinfunction "19_19") (pintype "bidirectional"))
    )
    (net (code "29") (name "Net-(EPD_C8-Pad1)") (class "Default")
      (node (ref "EPD_C8") (pin "1") (pinfunction "1_1") (pintype "passive"))
      (node (ref "J1") (pin "20") (pinfunction "20_20") (pintype "bidirectional"))
    )
    (net (code "30") (name "Net-(EPD_C10-Pad1)") (class "Default")
      (node (ref "EPD_C10") (pin "1") (pinfunction "1_1") (pintype "passive"))
      (node (ref "J1") (pin "22") (pinfunction "22_22") (pintype "bidirectional"))
    )
    (net (code "31") (name "Net-(EPD_C12-Pad1)") (class "Default")
      (node (ref "EPD_C12") (pin "1") (pinfunction "1_1") (pintype "passive"))
      (node (ref "J1") (pin "24") (pinfunction "24_24") (pintype "bidirectional"))
    )
    (net (code "32") (name "Net-(IC1-CT)") (class "Default")
      (node (ref "C_DELAY") (pin "1") (pinfunction "1_1") (pintype "passive"))
      (node (ref "IC1") (pin "5") (pinfunction "CT_5") (pintype "bidirectional"))
    )
    (net (code "33") (name "Net-(J2-PadA5)") (class "Default")
      (node (ref "J2") (pin "A5") (pinfunction "A5_A5") (pintype "bidirectional"))
      (node (ref "R2-USB1") (pin "2") (pinfunction "2_2") (pintype "passive"))
    )
    (net (code "34") (name "Net-(J2-PadB5)") (class "Default")
      (node (ref "J2") (pin "B5") (pinfunction "B5_B5") (pintype "bidirectional"))
      (node (ref "R2-USB") (pin "1") (pinfunction "1_1") (pintype "passive"))
    )
    (net (code "35") (name "Net-(MCP73831-PROG)") (class "Default")
      (node (ref "MCP73831") (pin "5") (pinfunction "PROG_5") (pintype "input"))
      (node (ref "R2_BAT") (pin "2") (pinfunction "2_2") (pintype "passive"))
    )
    (net (code "36") (name "Net-(MCP73831-STAT)") (class "Default")
      (node (ref "MCP73831") (pin "1") (pinfunction "STAT_1") (pintype "output"))
      (node (ref "R1_BAT") (pin "1") (pinfunction "1_1") (pintype "passive"))
    )
    (net (code "37") (name "PREVGH") (class "Default")
      (node (ref "D5") (pin "1") (pinfunction "K_1") (pintype "bidirectional"))
      (node (ref "EPD_C9") (pin "1") (pinfunction "1_1") (pintype "passive"))
      (node (ref "J1") (pin "21") (pinfunction "21_21") (pintype "bidirectional"))
    )
    (net (code "38") (name "PREVGL") (class "Default")
      (node (ref "D3") (pin "2") (pinfunction "A_2") (pintype "bidirectional"))
      (node (ref "EPD_C11") (pin "1") (pinfunction "1_1") (pintype "passive"))
      (node (ref "J1") (pin "23") (pinfunction "23_23") (pintype "bidirectional"))
    )
    (net (code "39") (name "RESE") (class "Default")
      (node (ref "J1") (pin "3") (pinfunction "3_3") (pintype "bidirectional"))
      (node (ref "Q3") (pin "2") (pinfunction "S_2") (pintype "bidirectional"))
      (node (ref "R3") (pin "1") (pinfunction "1_1") (pintype "passive"))
    )
    (net (code "40") (name "RESE'") (class "Default")
      (node (ref "R2") (pin "2") (pinfunction "2_2") (pintype "passive"))
      (node (ref "R3") (pin "2") (pinfunction "2_2") (pintype "passive"))
      (node (ref "SJ1") (pin "2") (pinfunction "2_2") (pintype "passive"))
    )
    (net (code "41") (name "RESET") (class "Default")
      (node (ref "C5") (pin "1") (pinfunction "1_1") (pintype "passive"))
      (node (ref "IC1") (pin "1") (pinfunction "VOUT_1") (pintype "bidirectional"))
      (node (ref "RESET_BUTTON") (pin "3") (pinfunction "3_3") (pintype "passive"))
      (node (ref "RESET_BUTTON") (pin "4") (pinfunction "4_4") (pintype "passive"))
      (node (ref "R_RESET") (pin "2") (pinfunction "2_2") (pintype "passive"))
      (node (ref "U2") (pin "3") (pinfunction "EN_3") (pintype "input"))
    )
    (net (code "42") (name "RTC_RST") (class "Default")
      (node (ref "U2") (pin "16") (pinfunction "IO18_16") (pintype "bidirectional"))
      (node (ref "U3") (pin "4") (pinfunction "~{RST}_4") (pintype "input"))
    )
    (net (code "43") (name "RX") (class "Default")
      (node (ref "RX") (pin "TP") (pinfunction "TP_TP") (pintype "input"))
      (node (ref "U2") (pin "24") (pinfunction "RXD0/GPIO17_24") (pintype "bidirectional"))
    )
    (net (code "44") (name "SCK") (class "Default")
      (node (ref "D10") (pin "2") (pinfunction "2_2") (pintype "passive"))
      (node (ref "J1") (pin "13") (pinfunction "13_13") (pintype "bidirectional"))
      (node (ref "J4") (pin "P5") (pinfunction "CLK_P5") (pintype "bidirectional"))
      (node (ref "R6") (pin "1") (pinfunction "1_1") (pintype "passive"))
      (node (ref "SCK") (pin "TP") (pinfunction "TP_TP") (pintype "input"))
      (node (ref "U1") (pin "6") (pinfunction "CLK_6") (pintype "input"))
      (node (ref "U2") (pin "6") (pinfunction "IO6_6") (pintype "bidirectional"))
    )
    (net (code "45") (name "SCL") (class "Default")
      (node (ref "J3") (pin "4") (pinfunction "4_4") (pintype "passive"))
      (node (ref "R2-PINH") (pin "1") (pinfunction "1_1") (pintype "passive"))
      (node (ref "SENSOR2") (pin "4") (pinfunction "SCK_4") (pintype "input"))
      (node (ref "U2") (pin "20") (pinfunction "IO22_20") (pintype "bidirectional"))
      (node (ref "U3") (pin "16") (pinfunction "SCL_16") (pintype "input"))
      (node (ref "U4") (pin "7") (pinfunction "SCL_7") (pintype "input"))
    )
    (net (code "46") (name "SDA") (class "Default")
      (node (ref "J3") (pin "3") (pinfunction "3_3") (pintype "passive"))
      (node (ref "R1-PINH") (pin "1") (pinfunction "1_1") (pintype "passive"))
      (node (ref "SENSOR2") (pin "3") (pinfunction "SDI_3") (pintype "bidirectional"))
      (node (ref "U2") (pin "19") (pinfunction "IO21_19") (pintype "bidirectional"))
      (node (ref "U3") (pin "15") (pinfunction "SDA_15") (pintype "bidirectional"))
      (node (ref "U4") (pin "8") (pinfunction "SDA_8") (pintype "bidirectional"))
    )
    (net (code "47") (name "SRC") (class "Default")
      (node (ref "C4") (pin "2") (pinfunction "2_2") (pintype "passive"))
      (node (ref "D5") (pin "2") (pinfunction "A_2") (pintype "bidirectional"))
      (node (ref "L1") (pin "1") (pinfunction "1_1") (pintype "passive"))
      (node (ref "Q3") (pin "3") (pinfunction "D_3") (pintype "bidirectional"))
    )
    (net (code "48") (name "SS_SD") (class "Default")
      (node (ref "D8") (pin "2") (pinfunction "2_2") (pintype "passive"))
      (node (ref "J4") (pin "P2") (pinfunction "CD/DAT3_P2") (pintype "bidirectional"))
      (node (ref "R10") (pin "1") (pinfunction "1_1") (pintype "passive"))
      (node (ref "U2") (pin "4") (pinfunction "IO4_4") (pintype "bidirectional"))
    )
    (net (code "49") (name "TX") (class "Default")
      (node (ref "TX") (pin "TP") (pinfunction "TP_TP") (pintype "input"))
      (node (ref "U2") (pin "25") (pinfunction "TXD0/GPIO16_25") (pintype "bidirectional"))
    )
    (net (code "50") (name "USB_D+") (class "Default")
      (node (ref "D1") (pin "1") (pinfunction "I/O1_1_1") (pintype "bidirectional"))
      (node (ref "U2") (pin "14") (pinfunction "IO13_14") (pintype "bidirectional"))
    )
    (net (code "51") (name "USB_D-") (class "Default")
      (node (ref "D1") (pin "3") (pinfunction "I/O2_1_3") (pintype "bidirectional"))
      (node (ref "U2") (pin "13") (pinfunction "IO12_13") (pintype "bidirectional"))
    )
    (net (code "52") (name "VBAT") (class "Default")
      (node (ref "C2_BAT") (pin "1") (pinfunction "1_1") (pintype "passive"))
      (node (ref "MCP73831") (pin "3") (pinfunction "VBAT_3") (pintype "power_in"))
      (node (ref "Q1") (pin "3") (pinfunction "D_3") (pintype "bidirectional"))
      (node (ref "U4") (pin "2") (pinfunction "CELL_2") (pintype "power_in"))
      (node (ref "U4") (pin "3") (pinfunction "VDD_3") (pintype "power_in"))
      (node (ref "VBAT") (pin "TP") (pinfunction "TP_TP") (pintype "input"))
    )
    (net (code "53") (name "VBUS") (class "Default")
      (node (ref "C1_BAT") (pin "1") (pinfunction "1_1") (pintype "passive"))
      (node (ref "C4_USB") (pin "1") (pinfunction "1_1") (pintype "passive"))
      (node (ref "C5_USB") (pin "1") (pinfunction "1_1") (pintype "passive"))
      (node (ref "CHG_LED") (pin "A") (pinfunction "A_A") (pintype "passive"))
      (node (ref "D1") (pin "5") (pinfunction "VBUS_5") (pintype "bidirectional"))
      (node (ref "D2") (pin "2") (pinfunction "ANODE_2") (pintype "bidirectional"))
      (node (ref "MCP73831") (pin "4") (pinfunction "VIN_4") (pintype "power_in"))
      (node (ref "PFMF.050.1") (pin "2") (pinfunction "2_2") (pintype "passive"))
      (node (ref "Q1") (pin "1") (pinfunction "G_1") (pintype "bidirectional"))
      (node (ref "R1_PWRUSB") (pin "2") (pinfunction "2_2") (pintype "passive"))
      (node (ref "VBUS") (pin "TP") (pinfunction "TP_TP") (pintype "input"))
    )
    (net (code "54") (name "VRTC") (class "Default")
      (node (ref "C10_SUPERCAP") (pin "2") (pinfunction "2_2") (pintype "passive"))
      (node (ref "C8") (pin "1") (pinfunction "1_1") (pintype "passive"))
      (node (ref "R_CAPACITOR") (pin "1") (pinfunction "1_1") (pintype "passive"))
      (node (ref "U3") (pin "14") (pinfunction "VBAT_14") (pintype "power_in"))
    )
    (net (code "55") (name "VUSB") (class "Default")
      (node (ref "J2") (pin "A4") (pinfunction "A4_A4") (pintype "bidirectional"))
      (node (ref "J2") (pin "A9") (pinfunction "A9_A9") (pintype "bidirectional"))
      (node (ref "J2") (pin "B4") (pinfunction "B4_B4") (pintype "bidirectional"))
      (node (ref "J2") (pin "B9") (pinfunction "B9_B9") (pintype "bidirectional"))
      (node (ref "PFMF.050.1") (pin "1") (pinfunction "1_1") (pintype "passive"))
    )
    (net (code "56") (name "unconnected-(IC1-NC-Pad4)") (class "Default")
      (node (ref "IC1") (pin "4") (pinfunction "NC_4") (pintype "no_connect"))
    )
    (net (code "57") (name "unconnected-(IC4-NC-Pad4)") (class "Default")
      (node (ref "IC4") (pin "4") (pinfunction "NC_4") (pintype "no_connect"))
    )
    (net (code "58") (name "unconnected-(J1-Pad1)") (class "Default")
      (node (ref "J1") (pin "1") (pinfunction "1_1") (pintype "bidirectional"))
    )
    (net (code "59") (name "unconnected-(J1-Pad6)") (class "Default")
      (node (ref "J1") (pin "6") (pinfunction "6_6") (pintype "bidirectional"))
    )
    (net (code "60") (name "unconnected-(J1-Pad7)") (class "Default")
      (node (ref "J1") (pin "7") (pinfunction "7_7") (pintype "bidirectional"))
    )
    (net (code "61") (name "unconnected-(J2-PadA8)") (class "Default")
      (node (ref "J2") (pin "A8") (pinfunction "A8_A8") (pintype "bidirectional"))
    )
    (net (code "62") (name "unconnected-(J2-PadB8)") (class "Default")
      (node (ref "J2") (pin "B8") (pinfunction "B8_B8") (pintype "bidirectional"))
    )
    (net (code "63") (name "unconnected-(J4-DAT1-PadP8)") (class "Default")
      (node (ref "J4") (pin "P8") (pinfunction "DAT1_P8") (pintype "bidirectional"))
    )
    (net (code "64") (name "unconnected-(J4-DAT2-PadP1)") (class "Default")
      (node (ref "J4") (pin "P1") (pinfunction "DAT2_P1") (pintype "bidirectional"))
    )
    (net (code "65") (name "unconnected-(J4-DETECTION_1-PadS1)") (class "Default")
      (node (ref "J4") (pin "S1") (pinfunction "DETECTION_1_S1") (pintype "bidirectional"))
    )
    (net (code "66") (name "unconnected-(J4-DETECTION_2-PadS2)") (class "Default")
      (node (ref "J4") (pin "S2") (pinfunction "DETECTION_2_S2") (pintype "bidirectional"))
    )
    (net (code "67") (name "unconnected-(U2-NC-Pad22)") (class "Default")
      (node (ref "U2") (pin "22") (pinfunction "NC_22") (pintype "no_connect"))
    )
    (net (code "68") (name "unconnected-(U4-~{ALERT}-Pad5)") (class "Default")
      (node (ref "U4") (pin "5") (pinfunction "~{ALERT}_5") (pintype "output"))
    )
  )
)
